# NUCLEO-F410RB-Core.net
KiCad netlist of a schematic drawn in Altium Designer
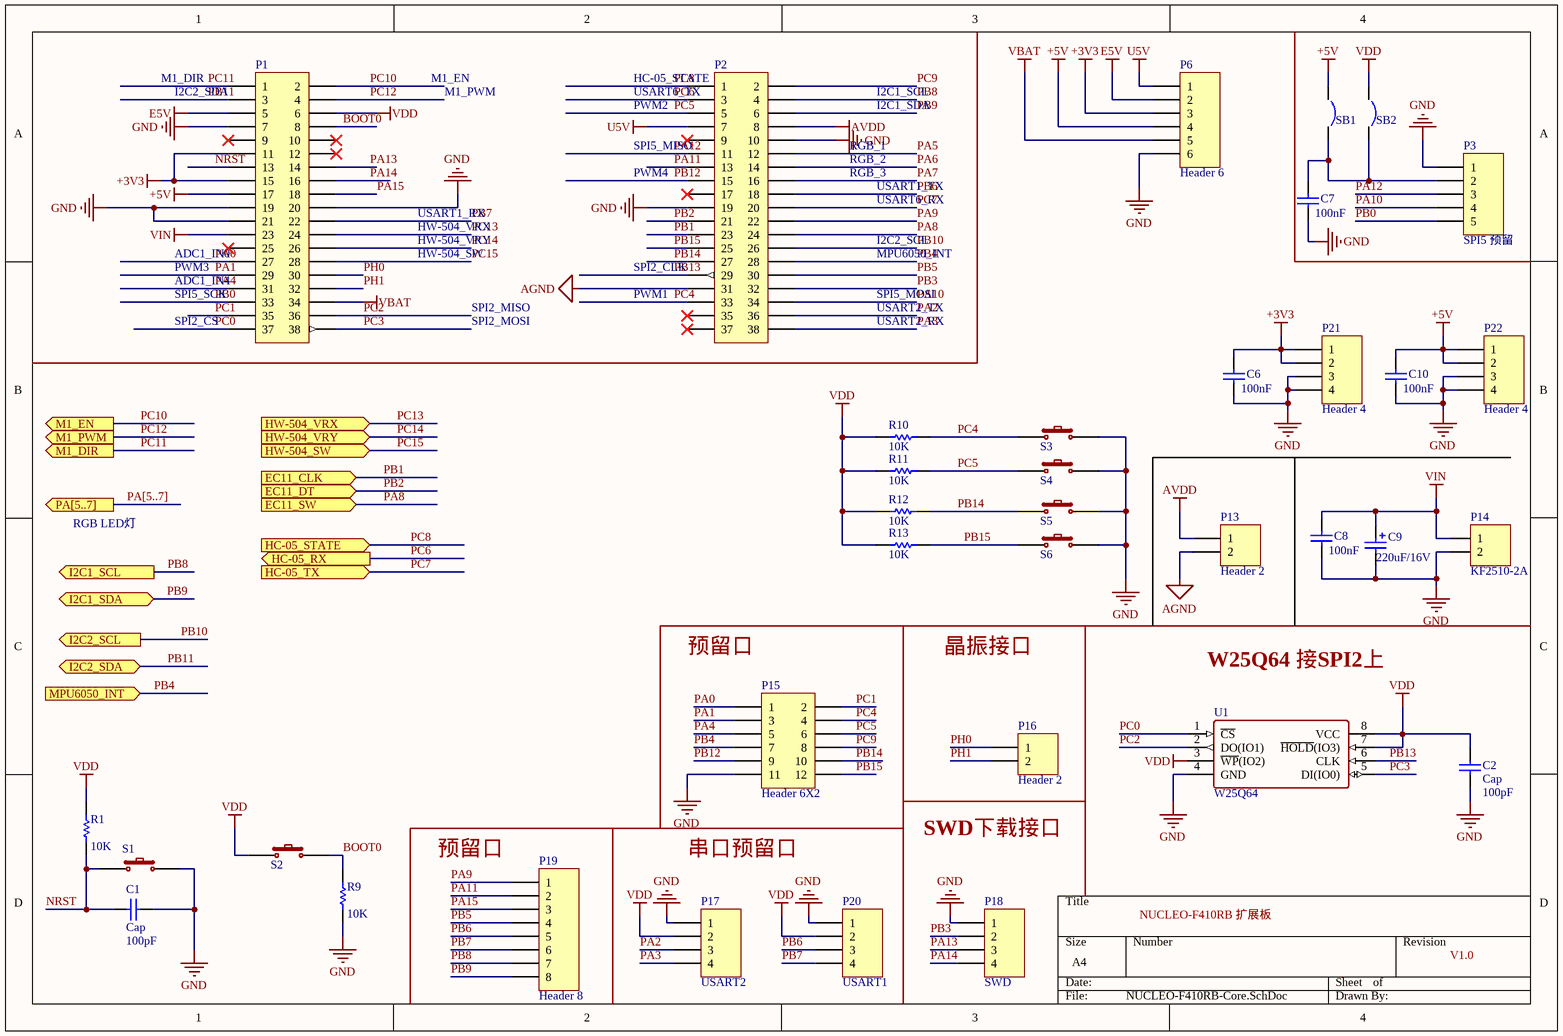
[diagram p0: NUCLEO-F410RB-Core.SchDoc]

(export (version "E")
  (design (tool "Eeschema 10.0.6"))
  (components
    (comp (ref "C1")
      (value "Cap")
      (footprint "C0603")
      (description "无极性电容")
      (fields (field (name "ALTIUM_VALUE") "100pF") (field (name "PUBLISHER") "Altium Limited"))
      (libsource (lib "Capacitor") (part "Cap"))
    )
    (comp (ref "C2")
      (value "Cap")
      (footprint "C0603")
      (description "无极性电容")
      (fields (field (name "ALTIUM_VALUE") "100pF") (field (name "PUBLISHER") "Altium Limited"))
      (libsource (lib "Capacitor") (part "Cap"))
    )
    (comp (ref "C6")
      (value "100nF")
      (footprint "C0603")
      (description "Capacitor")
      (fields (field (name "Comment") "Cap") (field (name "PUBLISHER") "Altium Limited"))
      (libsource (lib "baselib") (part "Cap"))
    )
    (comp (ref "C7")
      (value "100nF")
      (footprint "C0603")
      (description "Capacitor")
      (fields (field (name "Comment") "Cap") (field (name "PUBLISHER") "Altium Limited"))
      (libsource (lib "baselib") (part "Cap"))
    )
    (comp (ref "C8")
      (value "100nF")
      (footprint "C0603")
      (description "Capacitor")
      (fields (field (name "Comment") "Cap") (field (name "PUBLISHER") "Altium Limited"))
      (libsource (lib "baselib") (part "Cap"))
    )
    (comp (ref "C9")
      (value "220uF/16V")
      (footprint "CAP-TH_BD6.3-P2.50-D1.0-FD")
      (description "有极性电容")
      (fields (field (name "Comment") "Cap Pol1") (field (name "PUBLISHER") "信念D力量"))
      (libsource (lib "baselib") (part "Cap Pol1"))
    )
    (comp (ref "C10")
      (value "100nF")
      (footprint "C0603")
      (description "Capacitor")
      (fields (field (name "Comment") "Cap") (field (name "PUBLISHER") "Altium Limited"))
      (libsource (lib "baselib") (part "Cap"))
    )
    (comp (ref "P1")
      (value "HDR-F-2.54_2x19")
      (footprint "HDR2X19")
      (description "2.54mm 母头排针座")
      (fields (field (name "PUBLISHER") "Altium Limited"))
      (libsource (lib "Connectors") (part "HDR-F-2.54_2x19"))
    )
    (comp (ref "P2")
      (value "HDR-F-2.54_2x19")
      (footprint "HDR2X19")
      (description "2.54mm 母头排针座")
      (fields (field (name "PUBLISHER") "Altium Limited"))
      (libsource (lib "Connectors") (part "HDR-F-2.54_2x19"))
    )
    (comp (ref "P3")
      (value "SPI5 预留")
      (footprint "HDR1X5-Male")
      (description "Header, 5-Pin")
      (fields (field (name "PUBLISHER") "Altium Limited"))
      (libsource (lib "Connectors") (part "Header 5"))
    )
    (comp (ref "P6")
      (value "Header 6")
      (footprint "HDR1X6")
      (description "Header, 6-Pin")
      (fields (field (name "PUBLISHER") "Altium Limited"))
      (libsource (lib "Connectors") (part "Header 6"))
    )
    (comp (ref "P13")
      (value "Header 2")
      (footprint "HDR1X2")
      (description "Header, 2-Pin")
      (fields (field (name "PUBLISHER") "Altium Limited"))
      (libsource (lib "Connectors") (part "Header 2"))
    )
    (comp (ref "P14")
      (value "KF2510-2A")
      (footprint "KF2510-2A")
      (description "KF2510-2A 端子")
      (fields (field (name "PUBLISHER") "Altium Limited"))
      (libsource (lib "Connectors") (part "KF2510-2A"))
    )
    (comp (ref "P15")
      (value "Header 6X2")
      (footprint "HDR2X6")
      (description "Header, 6-Pin, Dual row")
      (fields (field (name "PUBLISHER") "Altium Limited"))
      (libsource (lib "Connectors") (part "Header 6X2"))
    )
    (comp (ref "P16")
      (value "Header 2")
      (footprint "HDR1X2")
      (description "Header, 2-Pin")
      (fields (field (name "PUBLISHER") "Altium Limited"))
      (libsource (lib "Connectors") (part "Header 2"))
    )
    (comp (ref "P17")
      (value "USART2")
      (footprint "HDR1X4-Male")
      (description "Header, 4-Pin")
      (fields (field (name "PUBLISHER") "Altium Limited"))
      (libsource (lib "Connectors") (part "Header 4"))
    )
    (comp (ref "P18")
      (value "SWD")
      (footprint "HDR1X4-Male")
      (description "Header, 4-Pin")
      (fields (field (name "PUBLISHER") "Altium Limited"))
      (libsource (lib "Connectors") (part "Header 4"))
    )
    (comp (ref "P19")
      (value "Header 8")
      (footprint "HDR1X8-Male")
      (description "Header, 8-Pin")
      (fields (field (name "PUBLISHER") "Altium Limited"))
      (libsource (lib "Connectors") (part "Header 8"))
    )
    (comp (ref "P20")
      (value "USART1")
      (footprint "HDR1X4-Male")
      (description "Header, 4-Pin")
      (fields (field (name "PUBLISHER") "Altium Limited"))
      (libsource (lib "Connectors") (part "Header 4"))
    )
    (comp (ref "P21")
      (value "Header 4")
      (footprint "HDR1X4-Male")
      (description "Header, 4-Pin")
      (fields (field (name "PUBLISHER") "Altium Limited"))
      (libsource (lib "Connectors") (part "Header 4"))
    )
    (comp (ref "P22")
      (value "Header 4")
      (footprint "HDR1X4-Male")
      (description "Header, 4-Pin")
      (fields (field (name "PUBLISHER") "Altium Limited"))
      (libsource (lib "Connectors") (part "Header 4"))
    )
    (comp (ref "R1")
      (value "10K")
      (footprint "R0603")
      (description "Resistor")
      (fields (field (name "Comment") "Res_US") (field (name "PUBLISHER") "Altium Limited"))
      (libsource (lib "baselib") (part "Res_US"))
    )
    (comp (ref "R9")
      (value "10K")
      (footprint "R0603")
      (description "Resistor")
      (fields (field (name "Comment") "Res_US") (field (name "PUBLISHER") "Altium Limited"))
      (libsource (lib "baselib") (part "Res_US"))
    )
    (comp (ref "R10")
      (value "10K")
      (footprint "R0603")
      (description "Resistor")
      (fields (field (name "Comment") "Res_US") (field (name "PUBLISHER") "Altium Limited"))
      (libsource (lib "baselib") (part "Res_US"))
    )
    (comp (ref "R11")
      (value "10K")
      (footprint "R0603")
      (description "Resistor")
      (fields (field (name "Comment") "Res_US") (field (name "PUBLISHER") "Altium Limited"))
      (libsource (lib "baselib") (part "Res_US"))
    )
    (comp (ref "R12")
      (value "10K")
      (footprint "R0603")
      (description "Resistor")
      (fields (field (name "Comment") "Res_US") (field (name "PUBLISHER") "Altium Limited"))
      (libsource (lib "baselib") (part "Res_US"))
    )
    (comp (ref "R13")
      (value "10K")
      (footprint "R0603")
      (description "Resistor")
      (fields (field (name "Comment") "Res_US") (field (name "PUBLISHER") "Altium Limited"))
      (libsource (lib "baselib") (part "Res_US"))
    )
    (comp (ref "S1")
      (value "K2-SMD_L6x_W3.5_LS8.0")
      (footprint "SW-SMD_L6.0-W3.5-LS8.0")
      (description "轻触开关 K2-SMD_L6x_W3.5_LS8.0")
      (fields (field (name "PUBLISHER") "Altium Limited"))
      (libsource (lib "baselib") (part "K2-SMD_L6x_W3.5_LS8.0"))
    )
    (comp (ref "S2")
      (value "K2-SMD_L6x_W3.5_LS8.0")
      (footprint "SW-SMD_L6.0-W3.5-LS8.0")
      (description "轻触开关 K2-SMD_L6x_W3.5_LS8.0")
      (fields (field (name "PUBLISHER") "Altium Limited"))
      (libsource (lib "baselib") (part "K2-SMD_L6x_W3.5_LS8.0"))
    )
    (comp (ref "S3")
      (value "K2-SMD_L6x_W3.5_LS8.0")
      (footprint "SW-SMD_L6.0-W3.5-LS8.0")
      (description "轻触开关 K2-SMD_L6x_W3.5_LS8.0")
      (fields (field (name "PUBLISHER") "Altium Limited"))
      (libsource (lib "baselib") (part "K2-SMD_L6x_W3.5_LS8.0"))
    )
    (comp (ref "S4")
      (value "K2-SMD_L6x_W3.5_LS8.0")
      (footprint "SW-SMD_L6.0-W3.5-LS8.0")
      (description "轻触开关 K2-SMD_L6x_W3.5_LS8.0")
      (fields (field (name "PUBLISHER") "Altium Limited"))
      (libsource (lib "baselib") (part "K2-SMD_L6x_W3.5_LS8.0"))
    )
    (comp (ref "S5")
      (value "K2-SMD_L6x_W3.5_LS8.0")
      (footprint "SW-SMD_L6.0-W3.5-LS8.0")
      (description "轻触开关 K2-SMD_L6x_W3.5_LS8.0")
      (fields (field (name "PUBLISHER") "Altium Limited"))
      (libsource (lib "baselib") (part "K2-SMD_L6x_W3.5_LS8.0"))
    )
    (comp (ref "S6")
      (value "K2-SMD_L6x_W3.5_LS8.0")
      (footprint "SW-SMD_L6.0-W3.5-LS8.0")
      (description "轻触开关 K2-SMD_L6x_W3.5_LS8.0")
      (fields (field (name "PUBLISHER") "Altium Limited"))
      (libsource (lib "baselib") (part "K2-SMD_L6x_W3.5_LS8.0"))
    )
    (comp (ref "SB1")
      (value "Circuit Breaker")
      (footprint "JP2_SMD")
      (fields (field (name "PUBLISHER") "Altium Limited"))
      (libsource (lib "baselib") (part "Circuit Breaker"))
    )
    (comp (ref "SB2")
      (value "Circuit Breaker")
      (footprint "JP2_SMD")
      (fields (field (name "PUBLISHER") "Altium Limited"))
      (libsource (lib "baselib") (part "Circuit Breaker"))
    )
    (comp (ref "U1")
      (value "W25Q64")
      (footprint "SOIC-8_208mil_L5.3-W5.3-P1.27-LS8.0-BL")
      (description "FLASH存储器")
      (libsource (lib "IC") (part "W25Q64"))
    )
  )
  (nets
    (net (code "1") (name "+3V3") (class "Default")
      (node (ref "C6") (pin "2") (pinfunction "2_2") (pintype "passive"))
      (node (ref "P1") (pin "11") (pinfunction "11_11") (pintype "passive"))
      (node (ref "P1") (pin "15") (pinfunction "15_15") (pintype "passive"))
      (node (ref "P21") (pin "1") (pinfunction "1_1") (pintype "passive"))
      (node (ref "P21") (pin "2") (pinfunction "2_2") (pintype "passive"))
      (node (ref "P6") (pin "3") (pinfunction "3_3") (pintype "passive"))
    )
    (net (code "2") (name "+5V") (class "Default")
      (node (ref "C10") (pin "2") (pinfunction "2_2") (pintype "passive"))
      (node (ref "P1") (pin "17") (pinfunction "17_17") (pintype "passive"))
      (node (ref "P22") (pin "1") (pinfunction "1_1") (pintype "passive"))
      (node (ref "P22") (pin "2") (pinfunction "2_2") (pintype "passive"))
      (node (ref "P6") (pin "4") (pinfunction "4_4") (pintype "passive"))
      (node (ref "SB1") (pin "1") (pinfunction "1_1") (pintype "passive"))
    )
    (net (code "3") (name "/BOOT0") (class "Default")
      (node (ref "P1") (pin "8") (pinfunction "8_8") (pintype "passive"))
      (node (ref "R9") (pin "2") (pinfunction "2_2") (pintype "passive"))
      (node (ref "S2") (pin "2") (pintype "passive"))
    )
    (net (code "4") (name "/NRST") (class "Default")
      (node (ref "C1") (pin "1") (pinfunction "1_1") (pintype "passive"))
      (node (ref "P1") (pin "13") (pinfunction "13_13") (pintype "passive"))
      (node (ref "R1") (pin "1") (pinfunction "1_1") (pintype "passive"))
      (node (ref "S1") (pin "1") (pintype "passive"))
    )
    (net (code "5") (name "/PA0") (class "Default")
      (node (ref "P1") (pin "27") (pinfunction "27_27") (pintype "passive"))
      (node (ref "P15") (pin "1") (pinfunction "1_1") (pintype "passive"))
    )
    (net (code "6") (name "/PA1") (class "Default")
      (node (ref "P1") (pin "29") (pinfunction "29_29") (pintype "passive"))
      (node (ref "P15") (pin "3") (pinfunction "3_3") (pintype "passive"))
    )
    (net (code "7") (name "/PA2") (class "Default")
      (node (ref "P17") (pin "3") (pinfunction "3_3") (pintype "passive"))
      (node (ref "P2") (pin "36") (pinfunction "36_36") (pintype "passive"))
    )
    (net (code "8") (name "/PA3") (class "Default")
      (node (ref "P17") (pin "4") (pinfunction "4_4") (pintype "passive"))
      (node (ref "P2") (pin "38") (pinfunction "38_38") (pintype "output"))
    )
    (net (code "9") (name "/PA4") (class "Default")
      (node (ref "P1") (pin "31") (pinfunction "31_31") (pintype "passive"))
      (node (ref "P15") (pin "5") (pinfunction "5_5") (pintype "passive"))
    )
    (net (code "10") (name "/PA5") (class "Default")
      (node (ref "P2") (pin "12") (pinfunction "12_12") (pintype "passive"))
    )
    (net (code "11") (name "/PA6") (class "Default")
      (node (ref "P2") (pin "14") (pinfunction "14_14") (pintype "passive"))
    )
    (net (code "12") (name "/PA7") (class "Default")
      (node (ref "P2") (pin "16") (pinfunction "16_16") (pintype "passive"))
    )
    (net (code "13") (name "/PA8") (class "Default")
      (node (ref "P2") (pin "24") (pinfunction "24_24") (pintype "passive"))
    )
    (net (code "14") (name "/PA9") (class "Default")
      (node (ref "P19") (pin "1") (pinfunction "1_1") (pintype "passive"))
      (node (ref "P2") (pin "22") (pinfunction "22_22") (pintype "passive"))
    )
    (net (code "15") (name "/PA10") (class "Default")
      (node (ref "P2") (pin "34") (pinfunction "34_34") (pintype "passive"))
      (node (ref "P3") (pin "4") (pinfunction "4_4") (pintype "passive"))
    )
    (net (code "16") (name "/PA11") (class "Default")
      (node (ref "P19") (pin "2") (pinfunction "2_2") (pintype "passive"))
      (node (ref "P2") (pin "13") (pinfunction "13_13") (pintype "passive"))
    )
    (net (code "17") (name "/PA12") (class "Default")
      (node (ref "P2") (pin "11") (pinfunction "11_11") (pintype "passive"))
      (node (ref "P3") (pin "3") (pinfunction "3_3") (pintype "passive"))
    )
    (net (code "18") (name "/PA13") (class "Default")
      (node (ref "P1") (pin "14") (pinfunction "14_14") (pintype "passive"))
      (node (ref "P18") (pin "3") (pinfunction "3_3") (pintype "passive"))
    )
    (net (code "19") (name "/PA14") (class "Default")
      (node (ref "P1") (pin "16") (pinfunction "16_16") (pintype "passive"))
      (node (ref "P18") (pin "4") (pinfunction "4_4") (pintype "passive"))
    )
    (net (code "20") (name "/PA15") (class "Default")
      (node (ref "P1") (pin "18") (pinfunction "18_18") (pintype "passive"))
      (node (ref "P19") (pin "3") (pinfunction "3_3") (pintype "passive"))
    )
    (net (code "22") (name "/PB0") (class "Default")
      (node (ref "P1") (pin "33") (pinfunction "33_33") (pintype "passive"))
      (node (ref "P3") (pin "5") (pinfunction "5_5") (pintype "passive"))
    )
    (net (code "23") (name "/PB1") (class "Default")
      (node (ref "P2") (pin "23") (pinfunction "23_23") (pintype "passive"))
    )
    (net (code "24") (name "/PB2") (class "Default")
      (node (ref "P2") (pin "21") (pinfunction "21_21") (pintype "passive"))
    )
    (net (code "25") (name "/PB3") (class "Default")
      (node (ref "P18") (pin "2") (pinfunction "2_2") (pintype "passive"))
      (node (ref "P2") (pin "32") (pinfunction "32_32") (pintype "passive"))
    )
    (net (code "26") (name "/PB4") (class "Default")
      (node (ref "P15") (pin "7") (pinfunction "7_7") (pintype "passive"))
      (node (ref "P2") (pin "28") (pinfunction "28_28") (pintype "passive"))
    )
    (net (code "27") (name "/PB5") (class "Default")
      (node (ref "P19") (pin "4") (pinfunction "4_4") (pintype "passive"))
      (node (ref "P2") (pin "30") (pinfunction "30_30") (pintype "passive"))
    )
    (net (code "28") (name "/PB6") (class "Default")
      (node (ref "P19") (pin "5") (pinfunction "5_5") (pintype "passive"))
      (node (ref "P2") (pin "18") (pinfunction "18_18") (pintype "passive"))
      (node (ref "P20") (pin "3") (pinfunction "3_3") (pintype "passive"))
    )
    (net (code "29") (name "/PB7") (class "Default")
      (node (ref "P1") (pin "22") (pinfunction "22_22") (pintype "passive"))
      (node (ref "P19") (pin "6") (pinfunction "6_6") (pintype "passive"))
      (node (ref "P20") (pin "4") (pinfunction "4_4") (pintype "passive"))
    )
    (net (code "30") (name "/PB8") (class "Default")
      (node (ref "P19") (pin "7") (pinfunction "7_7") (pintype "passive"))
      (node (ref "P2") (pin "4") (pinfunction "4_4") (pintype "passive"))
    )
    (net (code "31") (name "/PB9") (class "Default")
      (node (ref "P19") (pin "8") (pinfunction "8_8") (pintype "passive"))
      (node (ref "P2") (pin "6") (pinfunction "6_6") (pintype "passive"))
    )
    (net (code "32") (name "/PB10") (class "Default")
      (node (ref "P2") (pin "26") (pinfunction "26_26") (pintype "passive"))
    )
    (net (code "33") (name "/PB11") (class "Default")
      (node (ref "P1") (pin "3") (pinfunction "3_3") (pintype "passive"))
    )
    (net (code "34") (name "/PB12") (class "Default")
      (node (ref "P15") (pin "9") (pinfunction "9_9") (pintype "passive"))
      (node (ref "P2") (pin "15") (pinfunction "15_15") (pintype "passive"))
    )
    (net (code "35") (name "/PB13") (class "Default")
      (node (ref "P2") (pin "29") (pinfunction "29_29") (pintype "passive"))
      (node (ref "U1") (pin "6") (pinfunction "CLK_6") (pintype "input"))
    )
    (net (code "36") (name "/PB14") (class "Default")
      (node (ref "P15") (pin "10") (pinfunction "10_10") (pintype "passive"))
      (node (ref "P2") (pin "27") (pinfunction "27_27") (pintype "passive"))
      (node (ref "R12") (pin "1") (pinfunction "1_1") (pintype "passive"))
      (node (ref "S5") (pin "1") (pintype "passive"))
    )
    (net (code "37") (name "/PB15") (class "Default")
      (node (ref "P15") (pin "12") (pinfunction "12_12") (pintype "passive"))
      (node (ref "P2") (pin "25") (pinfunction "25_25") (pintype "passive"))
      (node (ref "R13") (pin "1") (pinfunction "1_1") (pintype "passive"))
      (node (ref "S6") (pin "1") (pintype "passive"))
    )
    (net (code "38") (name "/PC0") (class "Default")
      (node (ref "P1") (pin "37") (pinfunction "37_37") (pintype "passive"))
      (node (ref "U1") (pin "1") (pinfunction "~{CS}_1") (pintype "input"))
    )
    (net (code "39") (name "/PC1") (class "Default")
      (node (ref "P1") (pin "35") (pinfunction "35_35") (pintype "passive"))
      (node (ref "P15") (pin "2") (pinfunction "2_2") (pintype "passive"))
    )
    (net (code "40") (name "/PC2") (class "Default")
      (node (ref "P1") (pin "36") (pinfunction "36_36") (pintype "passive"))
      (node (ref "U1") (pin "2") (pinfunction "DO(IO1)_2") (pintype "output"))
    )
    (net (code "41") (name "/PC3") (class "Default")
      (node (ref "P1") (pin "38") (pinfunction "38_38") (pintype "output"))
      (node (ref "U1") (pin "5") (pinfunction "DI(IO0)_5") (pintype "bidirectional"))
    )
    (net (code "42") (name "/PC4") (class "Default")
      (node (ref "P15") (pin "4") (pinfunction "4_4") (pintype "passive"))
      (node (ref "P2") (pin "33") (pinfunction "33_33") (pintype "passive"))
      (node (ref "R10") (pin "1") (pinfunction "1_1") (pintype "passive"))
      (node (ref "S3") (pin "1") (pintype "passive"))
    )
    (net (code "43") (name "/PC5") (class "Default")
      (node (ref "P15") (pin "6") (pinfunction "6_6") (pintype "passive"))
      (node (ref "P2") (pin "5") (pinfunction "5_5") (pintype "passive"))
      (node (ref "R11") (pin "1") (pinfunction "1_1") (pintype "passive"))
      (node (ref "S4") (pin "1") (pintype "passive"))
    )
    (net (code "44") (name "/PC6") (class "Default")
      (node (ref "P2") (pin "3") (pinfunction "3_3") (pintype "passive"))
    )
    (net (code "45") (name "/PC7") (class "Default")
      (node (ref "P2") (pin "20") (pinfunction "20_20") (pintype "passive"))
    )
    (net (code "46") (name "/PC8") (class "Default")
      (node (ref "P2") (pin "1") (pinfunction "1_1") (pintype "passive"))
    )
    (net (code "47") (name "/PC9") (class "Default")
      (node (ref "P15") (pin "8") (pinfunction "8_8") (pintype "passive"))
      (node (ref "P2") (pin "2") (pinfunction "2_2") (pintype "passive"))
    )
    (net (code "48") (name "/PC10") (class "Default")
      (node (ref "P1") (pin "2") (pinfunction "2_2") (pintype "passive"))
    )
    (net (code "49") (name "/PC11") (class "Default")
      (node (ref "P1") (pin "1") (pinfunction "1_1") (pintype "passive"))
    )
    (net (code "50") (name "/PC12") (class "Default")
      (node (ref "P1") (pin "4") (pinfunction "4_4") (pintype "passive"))
    )
    (net (code "51") (name "/PC13") (class "Default")
      (node (ref "P1") (pin "24") (pinfunction "24_24") (pintype "passive"))
    )
    (net (code "52") (name "/PC14") (class "Default")
      (node (ref "P1") (pin "26") (pinfunction "26_26") (pintype "passive"))
    )
    (net (code "53") (name "/PC15") (class "Default")
      (node (ref "P1") (pin "28") (pinfunction "28_28") (pintype "passive"))
    )
    (net (code "54") (name "/PH0") (class "Default")
      (node (ref "P1") (pin "30") (pinfunction "30_30") (pintype "passive"))
      (node (ref "P16") (pin "1") (pinfunction "1_1") (pintype "passive"))
    )
    (net (code "55") (name "/PH1") (class "Default")
      (node (ref "P1") (pin "32") (pinfunction "32_32") (pintype "passive"))
      (node (ref "P16") (pin "2") (pinfunction "2_2") (pintype "passive"))
    )
    (net (code "56") (name "AGND") (class "Default")
      (node (ref "P13") (pin "2") (pinfunction "2_2") (pintype "passive"))
      (node (ref "P2") (pin "31") (pinfunction "31_31") (pintype "passive"))
    )
    (net (code "57") (name "AVDD") (class "Default")
      (node (ref "P13") (pin "1") (pinfunction "1_1") (pintype "passive"))
      (node (ref "P2") (pin "8") (pinfunction "8_8") (pintype "passive"))
    )
    (net (code "58") (name "E5V") (class "Default")
      (node (ref "P1") (pin "5") (pinfunction "5_5") (pintype "passive"))
      (node (ref "P6") (pin "2") (pinfunction "2_2") (pintype "passive"))
    )
    (net (code "59") (name "GND") (class "Default")
      (node (ref "C1") (pin "2") (pinfunction "2_2") (pintype "passive"))
      (node (ref "C10") (pin "1") (pinfunction "1_1") (pintype "passive"))
      (node (ref "C2") (pin "1") (pinfunction "1_1") (pintype "passive"))
      (node (ref "C6") (pin "1") (pinfunction "1_1") (pintype "passive"))
      (node (ref "C7") (pin "1") (pinfunction "1_1") (pintype "passive"))
      (node (ref "C8") (pin "1") (pinfunction "1_1") (pintype "passive"))
      (node (ref "C9") (pin "2") (pinfunction "2_2") (pintype "passive"))
      (node (ref "P1") (pin "19") (pinfunction "19_19") (pintype "passive"))
      (node (ref "P1") (pin "20") (pinfunction "20_20") (pintype "passive"))
      (node (ref "P1") (pin "21") (pinfunction "21_21") (pintype "passive"))
      (node (ref "P1") (pin "7") (pinfunction "7_7") (pintype "passive"))
      (node (ref "P14") (pin "2") (pinfunction "2_2") (pintype "passive"))
      (node (ref "P15") (pin "11") (pinfunction "11_11") (pintype "passive"))
      (node (ref "P17") (pin "1") (pinfunction "1_1") (pintype "passive"))
      (node (ref "P18") (pin "1") (pinfunction "1_1") (pintype "passive"))
      (node (ref "P2") (pin "10") (pinfunction "10_10") (pintype "passive"))
      (node (ref "P2") (pin "19") (pinfunction "19_19") (pintype "passive"))
      (node (ref "P20") (pin "1") (pinfunction "1_1") (pintype "passive"))
      (node (ref "P21") (pin "3") (pinfunction "3_3") (pintype "passive"))
      (node (ref "P21") (pin "4") (pinfunction "4_4") (pintype "passive"))
      (node (ref "P22") (pin "3") (pinfunction "3_3") (pintype "passive"))
      (node (ref "P22") (pin "4") (pinfunction "4_4") (pintype "passive"))
      (node (ref "P3") (pin "1") (pinfunction "1_1") (pintype "passive"))
      (node (ref "P6") (pin "6") (pinfunction "6_6") (pintype "passive"))
      (node (ref "R9") (pin "1") (pinfunction "1_1") (pintype "passive"))
      (node (ref "S1") (pin "2") (pintype "passive"))
      (node (ref "S3") (pin "2") (pintype "passive"))
      (node (ref "S4") (pin "2") (pintype "passive"))
      (node (ref "S5") (pin "2") (pintype "passive"))
      (node (ref "S6") (pin "2") (pintype "passive"))
      (node (ref "U1") (pin "4") (pinfunction "GND_4") (pintype "passive"))
    )
    (net (code "60") (name "Net-(C7-Pad2)") (class "Default")
      (node (ref "C7") (pin "2") (pinfunction "2_2") (pintype "passive"))
      (node (ref "P3") (pin "2") (pinfunction "2_2") (pintype "passive"))
      (node (ref "SB1") (pin "2") (pinfunction "2_2") (pintype "passive"))
      (node (ref "SB2") (pin "2") (pinfunction "2_2") (pintype "passive"))
    )
    (net (code "61") (name "U5V") (class "Default")
      (node (ref "P2") (pin "7") (pinfunction "7_7") (pintype "passive"))
      (node (ref "P6") (pin "1") (pinfunction "1_1") (pintype "passive"))
    )
    (net (code "62") (name "VBAT") (class "Default")
      (node (ref "P1") (pin "34") (pinfunction "34_34") (pintype "passive"))
      (node (ref "P6") (pin "5") (pinfunction "5_5") (pintype "passive"))
    )
    (net (code "63") (name "VDD") (class "Default")
      (node (ref "C2") (pin "2") (pinfunction "2_2") (pintype "passive"))
      (node (ref "P1") (pin "6") (pinfunction "6_6") (pintype "passive"))
      (node (ref "P17") (pin "2") (pinfunction "2_2") (pintype "passive"))
      (node (ref "P20") (pin "2") (pinfunction "2_2") (pintype "passive"))
      (node (ref "R1") (pin "2") (pinfunction "2_2") (pintype "passive"))
      (node (ref "R10") (pin "2") (pinfunction "2_2") (pintype "passive"))
      (node (ref "R11") (pin "2") (pinfunction "2_2") (pintype "passive"))
      (node (ref "R12") (pin "2") (pinfunction "2_2") (pintype "passive"))
      (node (ref "R13") (pin "2") (pinfunction "2_2") (pintype "passive"))
      (node (ref "S2") (pin "1") (pintype "passive"))
      (node (ref "SB2") (pin "1") (pinfunction "1_1") (pintype "passive"))
      (node (ref "U1") (pin "3") (pinfunction "~{WP}(IO2)_3") (pintype "passive"))
      (node (ref "U1") (pin "7") (pinfunction "~{HOLD}(IO3)_7") (pintype "input"))
      (node (ref "U1") (pin "8") (pinfunction "VCC_8") (pintype "passive"))
    )
    (net (code "64") (name "VIN") (class "Default")
      (node (ref "C8") (pin "2") (pinfunction "2_2") (pintype "passive"))
      (node (ref "C9") (pin "1") (pinfunction "1_1") (pintype "passive"))
      (node (ref "P1") (pin "23") (pinfunction "23_23") (pintype "passive"))
      (node (ref "P14") (pin "1") (pinfunction "1_1") (pintype "passive"))
    )
    (net (code "65") (name "unconnected-(P1-Pad9)") (class "Default")
      (node (ref "P1") (pin "9") (pinfunction "9_9") (pintype "passive+no_connect"))
    )
    (net (code "66") (name "unconnected-(P1-Pad10)") (class "Default")
      (node (ref "P1") (pin "10") (pinfunction "10_10") (pintype "passive+no_connect"))
    )
    (net (code "67") (name "unconnected-(P1-Pad12)") (class "Default")
      (node (ref "P1") (pin "12") (pinfunction "12_12") (pintype "passive+no_connect"))
    )
    (net (code "68") (name "unconnected-(P1-Pad25)") (class "Default")
      (node (ref "P1") (pin "25") (pinfunction "25_25") (pintype "passive+no_connect"))
    )
    (net (code "69") (name "unconnected-(P2-Pad9)") (class "Default")
      (node (ref "P2") (pin "9") (pinfunction "9_9") (pintype "passive+no_connect"))
    )
    (net (code "70") (name "unconnected-(P2-Pad17)") (class "Default")
      (node (ref "P2") (pin "17") (pinfunction "17_17") (pintype "passive+no_connect"))
    )
    (net (code "71") (name "unconnected-(P2-Pad35)") (class "Default")
      (node (ref "P2") (pin "35") (pinfunction "35_35") (pintype "passive+no_connect"))
    )
    (net (code "72") (name "unconnected-(P2-Pad37)") (class "Default")
      (node (ref "P2") (pin "37") (pinfunction "37_37") (pintype "passive+no_connect"))
    )
  )
)
